# design.net
KiCad netlist of a schematic drawn in Altium Designer
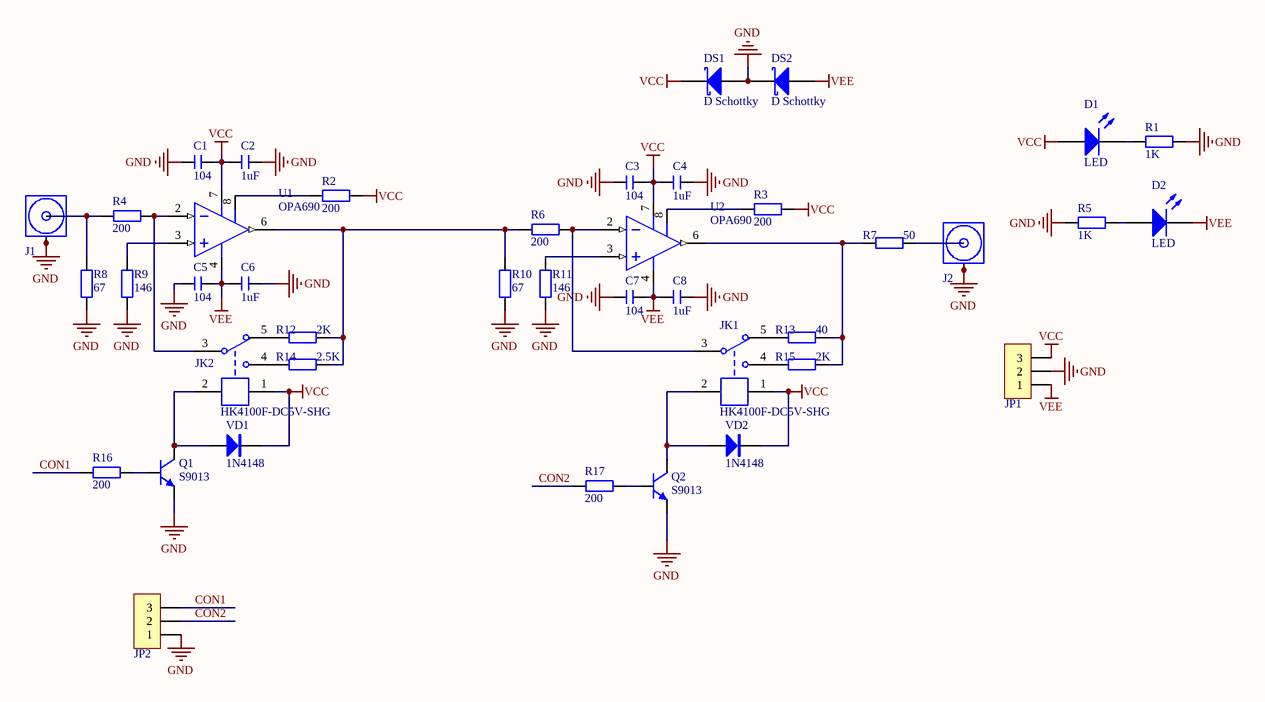
[diagram p0: 继电器程控放大.SchDoc]

(export (version "E")
  (design (tool "Eeschema 10.0.6"))
  (components
    (comp (ref "C1")
      (value "104")
      (footprint "C 0603")
      (description "无极性贴片电容")
      (fields (field (name "版权归属") "源创客"))
      (libsource (lib "电阻-电容-电感") (part "C"))
    )
    (comp (ref "C2")
      (value "1uF")
      (footprint "C 0603")
      (description "无极性贴片电容")
      (fields (field (name "版权归属") "源创客"))
      (libsource (lib "电阻-电容-电感") (part "C"))
    )
    (comp (ref "C3")
      (value "104")
      (footprint "C 0603")
      (description "无极性贴片电容")
      (fields (field (name "版权归属") "源创客"))
      (libsource (lib "电阻-电容-电感") (part "C"))
    )
    (comp (ref "C4")
      (value "1uF")
      (footprint "C 0603")
      (description "无极性贴片电容")
      (fields (field (name "版权归属") "源创客"))
      (libsource (lib "电阻-电容-电感") (part "C"))
    )
    (comp (ref "C5")
      (value "104")
      (footprint "C 0603")
      (description "无极性贴片电容")
      (fields (field (name "版权归属") "源创客"))
      (libsource (lib "电阻-电容-电感") (part "C"))
    )
    (comp (ref "C6")
      (value "1uF")
      (footprint "C 0603")
      (description "无极性贴片电容")
      (fields (field (name "版权归属") "源创客"))
      (libsource (lib "电阻-电容-电感") (part "C"))
    )
    (comp (ref "C7")
      (value "104")
      (footprint "C 0603")
      (description "无极性贴片电容")
      (fields (field (name "版权归属") "源创客"))
      (libsource (lib "电阻-电容-电感") (part "C"))
    )
    (comp (ref "C8")
      (value "1uF")
      (footprint "C 0603")
      (description "无极性贴片电容")
      (fields (field (name "版权归属") "源创客"))
      (libsource (lib "电阻-电容-电感") (part "C"))
    )
    (comp (ref "D1")
      (value "LED")
      (footprint "LED_0805")
      (description "发光二极管")
      (fields (field (name "PUBLISHER") "Altium Limited"))
      (libsource (lib "LIB") (part "LED"))
    )
    (comp (ref "D2")
      (value "LED")
      (footprint "LED_0805")
      (description "发光二极管")
      (fields (field (name "PUBLISHER") "Altium Limited"))
      (libsource (lib "LIB") (part "LED"))
    )
    (comp (ref "DS1")
      (value "D Schottky")
      (footprint "DIODE-SMA")
      (description "Schottky Diode")
      (fields (field (name "PUBLISHER") "Altium Limited"))
      (libsource (lib "LIB") (part "D Schottky"))
    )
    (comp (ref "DS2")
      (value "D Schottky")
      (footprint "DIODE-SMA")
      (description "Schottky Diode")
      (fields (field (name "PUBLISHER") "Altium Limited"))
      (libsource (lib "LIB") (part "D Schottky"))
    )
    (comp (ref "J1") (value "COAX") (footprint "MCX5.08-5-H") (libsource (lib "LIB") (part "COAX")))
    (comp (ref "J2") (value "COAX") (footprint "MCX5.08-5-H") (libsource (lib "LIB") (part "COAX")))
    (comp (ref "JK1")
      (value "HK4100F-DC5V-SHG")
      (footprint "HK4100F")
      (description "单路双控继电器")
      (fields (field (name "版权归属") "源创客"))
      (libsource (lib "继电器") (part "HK4100F"))
    )
    (comp (ref "JK2")
      (value "HK4100F-DC5V-SHG")
      (footprint "HK4100F")
      (description "单路双控继电器")
      (fields (field (name "版权归属") "源创客"))
      (libsource (lib "继电器") (part "HK4100F"))
    )
    (comp (ref "JP1")
      (value "HDR-1X3")
      (footprint "XH2.54-3P_H")
      (description "3P接插件")
      (fields (field (name "版权归属") "源创客"))
      (libsource (lib "接插件") (part "Header 3"))
    )
    (comp (ref "JP2")
      (value "HDR-1X3")
      (footprint "HDR-1X3")
      (description "3P接插件")
      (fields (field (name "版权归属") "源创客"))
      (libsource (lib "接插件") (part "Header 3"))
    )
    (comp (ref "Q1")
      (value "S9013")
      (footprint "SOT23-3N")
      (description "低频放大-NPN型")
      (fields (field (name "版权归属") "源创客"))
      (libsource (lib "三极管") (part "9013-SMD"))
    )
    (comp (ref "Q2")
      (value "S9013")
      (footprint "SOT23-3N")
      (description "低频放大-NPN型")
      (fields (field (name "版权归属") "源创客"))
      (libsource (lib "三极管") (part "9013-SMD"))
    )
    (comp (ref "R1")
      (value "1K")
      (footprint "R 0805")
      (description "贴片电阻")
      (fields (field (name "版权归属") "源创客"))
      (libsource (lib "电阻-电容-电感") (part "R"))
    )
    (comp (ref "R2")
      (value "200")
      (footprint "R 0603")
      (description "贴片电阻")
      (fields (field (name "版权归属") "源创客"))
      (libsource (lib "电阻-电容-电感") (part "R"))
    )
    (comp (ref "R3")
      (value "200")
      (footprint "R 0603")
      (description "贴片电阻")
      (fields (field (name "版权归属") "源创客"))
      (libsource (lib "电阻-电容-电感") (part "R"))
    )
    (comp (ref "R4")
      (value "200")
      (footprint "R 0603")
      (description "贴片电阻")
      (fields (field (name "版权归属") "源创客"))
      (libsource (lib "电阻-电容-电感") (part "R"))
    )
    (comp (ref "R5")
      (value "1K")
      (footprint "R 0805")
      (description "贴片电阻")
      (fields (field (name "版权归属") "源创客"))
      (libsource (lib "电阻-电容-电感") (part "R"))
    )
    (comp (ref "R6")
      (value "200")
      (footprint "R 0603")
      (description "贴片电阻")
      (fields (field (name "版权归属") "源创客"))
      (libsource (lib "电阻-电容-电感") (part "R"))
    )
    (comp (ref "R7")
      (value "50")
      (footprint "R 0603")
      (description "贴片电阻")
      (fields (field (name "版权归属") "源创客"))
      (libsource (lib "电阻-电容-电感") (part "R"))
    )
    (comp (ref "R8")
      (value "67")
      (footprint "R 0603")
      (description "贴片电阻")
      (fields (field (name "版权归属") "源创客"))
      (libsource (lib "电阻-电容-电感") (part "R"))
    )
    (comp (ref "R9")
      (value "146")
      (footprint "R 0603")
      (description "贴片电阻")
      (fields (field (name "版权归属") "源创客"))
      (libsource (lib "电阻-电容-电感") (part "R"))
    )
    (comp (ref "R10")
      (value "67")
      (footprint "R 0603")
      (description "贴片电阻")
      (fields (field (name "版权归属") "源创客"))
      (libsource (lib "电阻-电容-电感") (part "R"))
    )
    (comp (ref "R11")
      (value "146")
      (footprint "R 0603")
      (description "贴片电阻")
      (fields (field (name "版权归属") "源创客"))
      (libsource (lib "电阻-电容-电感") (part "R"))
    )
    (comp (ref "R12")
      (value "2K")
      (footprint "R 0603")
      (description "贴片电阻")
      (fields (field (name "版权归属") "源创客"))
      (libsource (lib "电阻-电容-电感") (part "R"))
    )
    (comp (ref "R13")
      (value "40")
      (footprint "R 0603")
      (description "贴片电阻")
      (fields (field (name "版权归属") "源创客"))
      (libsource (lib "电阻-电容-电感") (part "R"))
    )
    (comp (ref "R14")
      (value "2.5K")
      (footprint "R 0603")
      (description "贴片电阻")
      (fields (field (name "版权归属") "源创客"))
      (libsource (lib "电阻-电容-电感") (part "R"))
    )
    (comp (ref "R15")
      (value "2K")
      (footprint "R 0603")
      (description "贴片电阻")
      (fields (field (name "版权归属") "源创客"))
      (libsource (lib "电阻-电容-电感") (part "R"))
    )
    (comp (ref "R16")
      (value "200")
      (footprint "R 0603")
      (description "贴片电阻")
      (fields (field (name "版权归属") "源创客"))
      (libsource (lib "电阻-电容-电感") (part "R"))
    )
    (comp (ref "R17")
      (value "200")
      (footprint "R 0603")
      (description "贴片电阻")
      (fields (field (name "版权归属") "源创客"))
      (libsource (lib "电阻-电容-电感") (part "R"))
    )
    (comp (ref "U1")
      (value "OPA690")
      (footprint "LIB:SOIC8_N")
      (description "具有禁用功能的宽带电压反馈运算放大器")
      (libsource (lib "LIB") (part "OPA690ID"))
    )
    (comp (ref "U2")
      (value "OPA690")
      (footprint "LIB:SOIC8_N")
      (description "具有禁用功能的宽带电压反馈运算放大器")
      (libsource (lib "LIB") (part "OPA690ID"))
    )
    (comp (ref "VD1")
      (value "1N4148")
      (footprint "SOD-323")
      (description "高速开关二极管")
      (fields (field (name "版权归属") "源创客"))
      (libsource (lib "二极管-整流桥") (part "1N4148"))
    )
    (comp (ref "VD2")
      (value "1N4148")
      (footprint "SOD-323")
      (description "高速开关二极管")
      (fields (field (name "版权归属") "源创客"))
      (libsource (lib "二极管-整流桥") (part "1N4148"))
    )
  )
  (nets
    (net (code "1") (name "/CON1") (class "Default")
      (node (ref "JP2") (pin "3") (pinfunction "3_3") (pintype "passive"))
      (node (ref "R16") (pin "1") (pinfunction "1_1") (pintype "passive"))
    )
    (net (code "2") (name "/CON2") (class "Default")
      (node (ref "JP2") (pin "2") (pinfunction "2_2") (pintype "passive"))
      (node (ref "R17") (pin "1") (pinfunction "1_1") (pintype "passive"))
    )
    (net (code "3") (name "GND") (class "Default")
      (node (ref "C1") (pin "1") (pinfunction "1_1") (pintype "passive"))
      (node (ref "C2") (pin "2") (pinfunction "2_2") (pintype "passive"))
      (node (ref "C3") (pin "1") (pinfunction "1_1") (pintype "passive"))
      (node (ref "C4") (pin "2") (pinfunction "2_2") (pintype "passive"))
      (node (ref "C5") (pin "1") (pinfunction "1_1") (pintype "passive"))
      (node (ref "C6") (pin "2") (pinfunction "2_2") (pintype "passive"))
      (node (ref "C7") (pin "1") (pinfunction "1_1") (pintype "passive"))
      (node (ref "C8") (pin "2") (pinfunction "2_2") (pintype "passive"))
      (node (ref "DS1") (pin "1") (pinfunction "1_1") (pintype "passive"))
      (node (ref "DS2") (pin "2") (pinfunction "2_2") (pintype "passive"))
      (node (ref "J1") (pin "2") (pinfunction "GND_2") (pintype "passive"))
      (node (ref "J1") (pin "3") (pinfunction "GND_3") (pintype "passive"))
      (node (ref "J1") (pin "4") (pinfunction "GND_4") (pintype "passive"))
      (node (ref "J1") (pin "5") (pinfunction "GND_5") (pintype "passive"))
      (node (ref "J2") (pin "2") (pinfunction "GND_2") (pintype "passive"))
      (node (ref "J2") (pin "3") (pinfunction "GND_3") (pintype "passive"))
      (node (ref "J2") (pin "4") (pinfunction "GND_4") (pintype "passive"))
      (node (ref "J2") (pin "5") (pinfunction "GND_5") (pintype "passive"))
      (node (ref "JP1") (pin "2") (pinfunction "2_2") (pintype "passive"))
      (node (ref "JP2") (pin "1") (pinfunction "1_1") (pintype "passive"))
      (node (ref "Q1") (pin "2") (pinfunction "E_2") (pintype "passive"))
      (node (ref "Q2") (pin "2") (pinfunction "E_2") (pintype "passive"))
      (node (ref "R1") (pin "2") (pinfunction "2_2") (pintype "passive"))
      (node (ref "R10") (pin "2") (pinfunction "2_2") (pintype "passive"))
      (node (ref "R11") (pin "2") (pinfunction "2_2") (pintype "passive"))
      (node (ref "R5") (pin "1") (pinfunction "1_1") (pintype "passive"))
      (node (ref "R8") (pin "2") (pinfunction "2_2") (pintype "passive"))
      (node (ref "R9") (pin "1") (pinfunction "1_1") (pintype "passive"))
    )
    (net (code "4") (name "Net-(D1-K)") (class "Default")
      (node (ref "D1") (pin "2") (pinfunction "K_2") (pintype "passive"))
      (node (ref "R1") (pin "1") (pinfunction "1_1") (pintype "passive"))
    )
    (net (code "5") (name "Net-(D2-A)") (class "Default")
      (node (ref "D2") (pin "1") (pinfunction "A_1") (pintype "passive"))
      (node (ref "R5") (pin "2") (pinfunction "2_2") (pintype "passive"))
    )
    (net (code "6") (name "Net-(J1-Signal)") (class "Default")
      (node (ref "J1") (pin "1") (pinfunction "Signal_1") (pintype "passive"))
      (node (ref "R4") (pin "2") (pinfunction "2_2") (pintype "passive"))
      (node (ref "R8") (pin "1") (pinfunction "1_1") (pintype "passive"))
    )
    (net (code "7") (name "Net-(J2-Signal)") (class "Default")
      (node (ref "J2") (pin "1") (pinfunction "Signal_1") (pintype "passive"))
      (node (ref "R7") (pin "1") (pinfunction "1_1") (pintype "passive"))
    )
    (net (code "8") (name "Net-(JK1-Pad4)") (class "Default")
      (node (ref "JK1") (pin "4") (pinfunction "4_4") (pintype "passive"))
      (node (ref "R15") (pin "2") (pinfunction "2_2") (pintype "passive"))
    )
    (net (code "9") (name "Net-(JK1-Pad5)") (class "Default")
      (node (ref "JK1") (pin "5") (pinfunction "5_5") (pintype "passive"))
      (node (ref "R13") (pin "2") (pinfunction "2_2") (pintype "passive"))
    )
    (net (code "10") (name "Net-(JK2-Pad4)") (class "Default")
      (node (ref "JK2") (pin "4") (pinfunction "4_4") (pintype "passive"))
      (node (ref "R14") (pin "1") (pinfunction "1_1") (pintype "passive"))
    )
    (net (code "11") (name "Net-(JK2-Pad5)") (class "Default")
      (node (ref "JK2") (pin "5") (pinfunction "5_5") (pintype "passive"))
      (node (ref "R12") (pin "1") (pinfunction "1_1") (pintype "passive"))
    )
    (net (code "12") (name "Net-(Q1-B)") (class "Default")
      (node (ref "Q1") (pin "1") (pinfunction "B_1") (pintype "passive"))
      (node (ref "R16") (pin "2") (pinfunction "2_2") (pintype "passive"))
    )
    (net (code "13") (name "Net-(Q1-C)") (class "Default")
      (node (ref "JK2") (pin "2") (pinfunction "2_2") (pintype "passive"))
      (node (ref "Q1") (pin "3") (pinfunction "C_3") (pintype "passive"))
      (node (ref "VD1") (pin "1") (pinfunction "A_1") (pintype "passive"))
    )
    (net (code "14") (name "Net-(Q2-B)") (class "Default")
      (node (ref "Q2") (pin "1") (pinfunction "B_1") (pintype "passive"))
      (node (ref "R17") (pin "2") (pinfunction "2_2") (pintype "passive"))
    )
    (net (code "15") (name "Net-(Q2-C)") (class "Default")
      (node (ref "JK1") (pin "2") (pinfunction "2_2") (pintype "passive"))
      (node (ref "Q2") (pin "3") (pinfunction "C_3") (pintype "passive"))
      (node (ref "VD2") (pin "1") (pinfunction "A_1") (pintype "passive"))
    )
    (net (code "16") (name "Net-(U1-DIS)") (class "Default")
      (node (ref "R2") (pin "2") (pinfunction "2_2") (pintype "passive"))
      (node (ref "U1") (pin "8") (pinfunction "DIS_8") (pintype "passive"))
    )
    (net (code "17") (name "Net-(U1-IN+)") (class "Default")
      (node (ref "R9") (pin "2") (pinfunction "2_2") (pintype "passive"))
      (node (ref "U1") (pin "3") (pinfunction "IN+_3") (pintype "input"))
    )
    (net (code "18") (name "Net-(U1-IN-)") (class "Default")
      (node (ref "JK2") (pin "3") (pinfunction "3_3") (pintype "passive"))
      (node (ref "R4") (pin "1") (pinfunction "1_1") (pintype "passive"))
      (node (ref "U1") (pin "2") (pinfunction "IN-_2") (pintype "input"))
    )
    (net (code "19") (name "Net-(U1-OUT)") (class "Default")
      (node (ref "R10") (pin "1") (pinfunction "1_1") (pintype "passive"))
      (node (ref "R12") (pin "2") (pinfunction "2_2") (pintype "passive"))
      (node (ref "R14") (pin "2") (pinfunction "2_2") (pintype "passive"))
      (node (ref "R6") (pin "2") (pinfunction "2_2") (pintype "passive"))
      (node (ref "U1") (pin "6") (pinfunction "OUT_6") (pintype "output"))
    )
    (net (code "20") (name "Net-(U2-DIS)") (class "Default")
      (node (ref "R3") (pin "2") (pinfunction "2_2") (pintype "passive"))
      (node (ref "U2") (pin "8") (pinfunction "DIS_8") (pintype "passive"))
    )
    (net (code "21") (name "Net-(U2-IN+)") (class "Default")
      (node (ref "R11") (pin "1") (pinfunction "1_1") (pintype "passive"))
      (node (ref "U2") (pin "3") (pinfunction "IN+_3") (pintype "input"))
    )
    (net (code "22") (name "Net-(U2-IN-)") (class "Default")
      (node (ref "JK1") (pin "3") (pinfunction "3_3") (pintype "passive"))
      (node (ref "R6") (pin "1") (pinfunction "1_1") (pintype "passive"))
      (node (ref "U2") (pin "2") (pinfunction "IN-_2") (pintype "input"))
    )
    (net (code "23") (name "Net-(U2-OUT)") (class "Default")
      (node (ref "R13") (pin "1") (pinfunction "1_1") (pintype "passive"))
      (node (ref "R15") (pin "1") (pinfunction "1_1") (pintype "passive"))
      (node (ref "R7") (pin "2") (pinfunction "2_2") (pintype "passive"))
      (node (ref "U2") (pin "6") (pinfunction "OUT_6") (pintype "output"))
    )
    (net (code "24") (name "VCC") (class "Default")
      (node (ref "C1") (pin "2") (pinfunction "2_2") (pintype "passive"))
      (node (ref "C2") (pin "1") (pinfunction "1_1") (pintype "passive"))
      (node (ref "C3") (pin "2") (pinfunction "2_2") (pintype "passive"))
      (node (ref "C4") (pin "1") (pinfunction "1_1") (pintype "passive"))
      (node (ref "D1") (pin "1") (pinfunction "A_1") (pintype "passive"))
      (node (ref "DS1") (pin "2") (pinfunction "2_2") (pintype "passive"))
      (node (ref "JK1") (pin "1") (pinfunction "1_1") (pintype "passive"))
      (node (ref "JK2") (pin "1") (pinfunction "1_1") (pintype "passive"))
      (node (ref "JP1") (pin "3") (pinfunction "3_3") (pintype "passive"))
      (node (ref "R2") (pin "1") (pinfunction "1_1") (pintype "passive"))
      (node (ref "R3") (pin "1") (pinfunction "1_1") (pintype "passive"))
      (node (ref "U1") (pin "7") (pinfunction "V+_7") (pintype "power_in"))
      (node (ref "U2") (pin "7") (pinfunction "V+_7") (pintype "power_in"))
      (node (ref "VD1") (pin "2") (pinfunction "K_2") (pintype "passive"))
      (node (ref "VD2") (pin "2") (pinfunction "K_2") (pintype "passive"))
    )
    (net (code "25") (name "VEE") (class "Default")
      (node (ref "C5") (pin "2") (pinfunction "2_2") (pintype "passive"))
      (node (ref "C6") (pin "1") (pinfunction "1_1") (pintype "passive"))
      (node (ref "C7") (pin "2") (pinfunction "2_2") (pintype "passive"))
      (node (ref "C8") (pin "1") (pinfunction "1_1") (pintype "passive"))
      (node (ref "D2") (pin "2") (pinfunction "K_2") (pintype "passive"))
      (node (ref "DS2") (pin "1") (pinfunction "1_1") (pintype "passive"))
      (node (ref "JP1") (pin "1") (pinfunction "1_1") (pintype "passive"))
      (node (ref "U1") (pin "4") (pinfunction "V-_4") (pintype "power_in"))
      (node (ref "U2") (pin "4") (pinfunction "V-_4") (pintype "power_in"))
    )
  )
)
